# TRACKING_IF.net
KiCad netlist of a schematic drawn in EAGLE
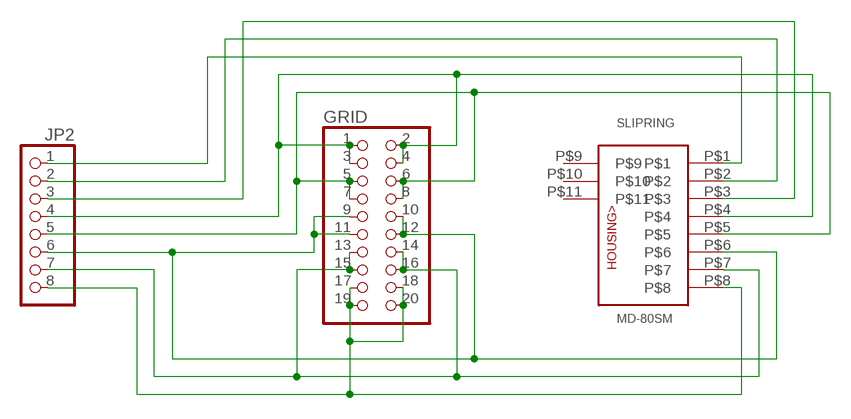
[diagram p0: schematic, sheet 1]

(export (version "E")
  (design (tool "Eeschema 10.0.6"))
  (components
    (comp (ref "GRID")
      (value "PINHD-2X10")
      (footprint "eagle-import:2X10")
      (libsource (lib "eagle-import") (part "PINHD-2X10"))
    )
    (comp (ref "JP2")
      (value "PINHD-1X8")
      (footprint "eagle-import:1X08")
      (libsource (lib "eagle-import") (part "PINHD-1X8"))
    )
    (comp (ref "SLIPRING")
      (value "MD-80SM")
      (footprint "eagle-import:MINIDIN8PCB")
      (libsource (lib "eagle-import") (part "MD-80SM"))
    )
  )
  (nets
    (net (code "1") (name "Net-(GRID-Pad1)") (class "Default")
      (node (ref "GRID") (pin "1") (pinfunction "1_1") (pintype "passive"))
      (node (ref "GRID") (pin "2") (pinfunction "2_2") (pintype "passive"))
      (node (ref "GRID") (pin "3") (pinfunction "3_3") (pintype "passive"))
      (node (ref "GRID") (pin "4") (pinfunction "4_4") (pintype "passive"))
      (node (ref "JP2") (pin "4") (pinfunction "4_4") (pintype "passive"))
      (node (ref "SLIPRING") (pin "P$4") (pinfunction "P$4_P$4") (pintype "bidirectional"))
    )
    (net (code "2") (name "Net-(GRID-Pad5)") (class "Default")
      (node (ref "GRID") (pin "5") (pinfunction "5_5") (pintype "passive"))
      (node (ref "GRID") (pin "6") (pinfunction "6_6") (pintype "passive"))
      (node (ref "GRID") (pin "7") (pinfunction "7_7") (pintype "passive"))
      (node (ref "GRID") (pin "8") (pinfunction "8_8") (pintype "passive"))
      (node (ref "JP2") (pin "5") (pinfunction "5_5") (pintype "passive"))
      (node (ref "SLIPRING") (pin "P$5") (pinfunction "P$5_P$5") (pintype "bidirectional"))
    )
    (net (code "3") (name "Net-(GRID-Pad10)") (class "Default")
      (node (ref "GRID") (pin "10") (pinfunction "10_10") (pintype "passive"))
      (node (ref "GRID") (pin "11") (pinfunction "11_11") (pintype "passive"))
      (node (ref "GRID") (pin "12") (pinfunction "12_12") (pintype "passive"))
      (node (ref "GRID") (pin "9") (pinfunction "9_9") (pintype "passive"))
      (node (ref "JP2") (pin "6") (pinfunction "6_6") (pintype "passive"))
      (node (ref "SLIPRING") (pin "P$6") (pinfunction "P$6_P$6") (pintype "bidirectional"))
    )
    (net (code "4") (name "Net-(GRID-Pad13)") (class "Default")
      (node (ref "GRID") (pin "13") (pinfunction "13_13") (pintype "passive"))
      (node (ref "GRID") (pin "14") (pinfunction "14_14") (pintype "passive"))
      (node (ref "GRID") (pin "15") (pinfunction "15_15") (pintype "passive"))
      (node (ref "GRID") (pin "16") (pinfunction "16_16") (pintype "passive"))
      (node (ref "JP2") (pin "7") (pinfunction "7_7") (pintype "passive"))
      (node (ref "SLIPRING") (pin "P$7") (pinfunction "P$7_P$7") (pintype "bidirectional"))
    )
    (net (code "5") (name "Net-(GRID-Pad17)") (class "Default")
      (node (ref "GRID") (pin "17") (pinfunction "17_17") (pintype "passive"))
      (node (ref "GRID") (pin "18") (pinfunction "18_18") (pintype "passive"))
      (node (ref "GRID") (pin "19") (pinfunction "19_19") (pintype "passive"))
      (node (ref "GRID") (pin "20") (pinfunction "20_20") (pintype "passive"))
      (node (ref "JP2") (pin "8") (pinfunction "8_8") (pintype "passive"))
      (node (ref "SLIPRING") (pin "P$8") (pinfunction "P$8_P$8") (pintype "bidirectional"))
    )
    (net (code "6") (name "Net-(JP2-Pad1)") (class "Default")
      (node (ref "JP2") (pin "1") (pinfunction "1_1") (pintype "passive"))
      (node (ref "SLIPRING") (pin "P$1") (pinfunction "P$1_P$1") (pintype "bidirectional"))
    )
    (net (code "7") (name "Net-(JP2-Pad2)") (class "Default")
      (node (ref "JP2") (pin "2") (pinfunction "2_2") (pintype "passive"))
      (node (ref "SLIPRING") (pin "P$2") (pinfunction "P$2_P$2") (pintype "bidirectional"))
    )
    (net (code "8") (name "Net-(JP2-Pad3)") (class "Default")
      (node (ref "JP2") (pin "3") (pinfunction "3_3") (pintype "passive"))
      (node (ref "SLIPRING") (pin "P$3") (pinfunction "P$3_P$3") (pintype "bidirectional"))
    )
    (net (code "9") (name "unconnected-(SLIPRING-PadP$9)") (class "Default")
      (node (ref "SLIPRING") (pin "P$9") (pinfunction "P$9_P$9") (pintype "bidirectional"))
    )
    (net (code "10") (name "unconnected-(SLIPRING-PadP$10)") (class "Default")
      (node (ref "SLIPRING") (pin "P$10") (pinfunction "P$10_P$10") (pintype "bidirectional"))
    )
    (net (code "11") (name "unconnected-(SLIPRING-PadP$11)") (class "Default")
      (node (ref "SLIPRING") (pin "P$11") (pinfunction "P$11_P$11") (pintype "bidirectional"))
    )
  )
)
